# USB_Interface.net
KiCad netlist of a schematic drawn in Altium Designer
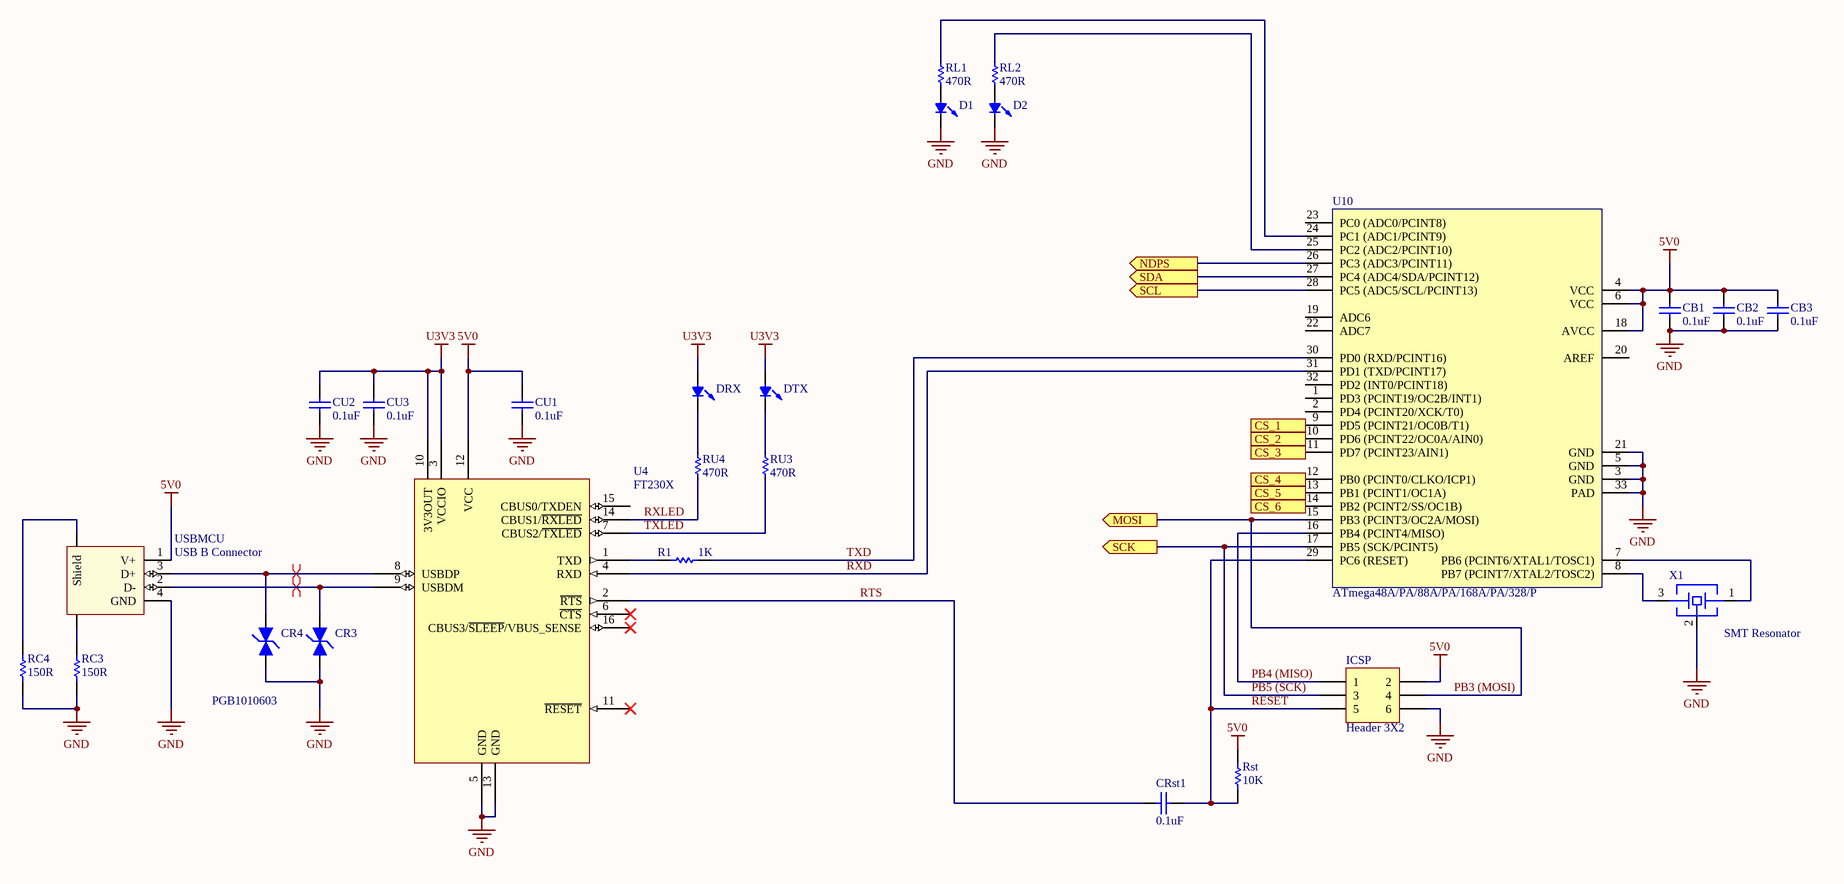
[diagram p0: USB Interface.SchDoc]

(export (version "E")
  (design (tool "Eeschema 10.0.6"))
  (components
    (comp (ref "CB1")
      (value "0.1uF")
      (footprint "0603C")
      (description "Capacitor (Semiconductor SIM Model)")
      (fields (field (name "Comment") "Cap Semi") (field (name "PUBLISHER") "Altium Limited"))
      (libsource (lib "Miscellaneous Devices") (part "Cap Semi"))
    )
    (comp (ref "CB2")
      (value "0.1uF")
      (footprint "0603C")
      (description "Capacitor (Semiconductor SIM Model)")
      (fields (field (name "Comment") "Cap Semi") (field (name "PUBLISHER") "Altium Limited"))
      (libsource (lib "Miscellaneous Devices") (part "Cap Semi"))
    )
    (comp (ref "CB3")
      (value "0.1uF")
      (footprint "0603C")
      (description "Capacitor (Semiconductor SIM Model)")
      (fields (field (name "Comment") "Cap Semi") (field (name "PUBLISHER") "Altium Limited"))
      (libsource (lib "Miscellaneous Devices") (part "Cap Semi"))
    )
    (comp (ref "CR3")
      (value "PGB1010603")
      (footprint "0603PG")
      (description "PulseGuard® Lead-Free 0603 Surface Mount Polymeric ESD Suppressors")
      (libsource (lib "DAQ System") (part "PGB1010603"))
    )
    (comp (ref "CR4")
      (value "PGB1010603")
      (footprint "0603PG")
      (description "PulseGuard® Lead-Free 0603 Surface Mount Polymeric ESD Suppressors")
      (libsource (lib "DAQ System") (part "PGB1010603"))
    )
    (comp (ref "CRst1")
      (value "0.1uF")
      (footprint "0603C")
      (description "Capacitor (Semiconductor SIM Model)")
      (fields (field (name "Comment") "Cap Semi") (field (name "PUBLISHER") "Altium Limited"))
      (libsource (lib "Miscellaneous Devices") (part "Cap Semi"))
    )
    (comp (ref "CU1")
      (value "0.1uF")
      (footprint "0603C")
      (description "Capacitor (Semiconductor SIM Model)")
      (fields (field (name "Comment") "Cap Semi") (field (name "PUBLISHER") "Altium Limited"))
      (libsource (lib "Miscellaneous Devices") (part "Cap Semi"))
    )
    (comp (ref "CU2")
      (value "0.1uF")
      (footprint "0603C")
      (description "Capacitor (Semiconductor SIM Model)")
      (fields (field (name "Comment") "Cap Semi") (field (name "PUBLISHER") "Altium Limited"))
      (libsource (lib "Miscellaneous Devices") (part "Cap Semi"))
    )
    (comp (ref "CU3")
      (value "0.1uF")
      (footprint "0603C")
      (description "Capacitor (Semiconductor SIM Model)")
      (fields (field (name "Comment") "Cap Semi") (field (name "PUBLISHER") "Altium Limited"))
      (libsource (lib "Miscellaneous Devices") (part "Cap Semi"))
    )
    (comp (ref "D1")
      (value "LED0")
      (footprint "T1 LED")
      (description "T 1 3/4 LED")
      (fields (field (name "PUBLISHER") "Altium Limited"))
      (libsource (lib "Miscellaneous Devices") (part "LED0"))
    )
    (comp (ref "D2")
      (value "LED0")
      (footprint "T1 LED")
      (description "T 1 3/4 LED")
      (fields (field (name "PUBLISHER") "Altium Limited"))
      (libsource (lib "Miscellaneous Devices") (part "LED0"))
    )
    (comp (ref "DRX")
      (value "LED0")
      (footprint "T1 LED")
      (description "T 1 3/4 LED")
      (fields (field (name "PUBLISHER") "Altium Limited"))
      (libsource (lib "Miscellaneous Devices") (part "LED0"))
    )
    (comp (ref "DTX")
      (value "LED0")
      (footprint "T1 LED")
      (description "T 1 3/4 LED")
      (fields (field (name "PUBLISHER") "Altium Limited"))
      (libsource (lib "Miscellaneous Devices") (part "LED0"))
    )
    (comp (ref "ICSP")
      (value "Header 3X2")
      (footprint "HDR2X3")
      (description "Header, 3-Pin, Dual row")
      (fields (field (name "PUBLISHER") "Altium Limited"))
      (libsource (lib "Miscellaneous Connectors") (part "Header 3X2"))
    )
    (comp (ref "R1")
      (value "1K")
      (footprint "0603R")
      (description "Semiconductor Resistor")
      (fields (field (name "Comment") "Res Semi") (field (name "PUBLISHER") "Altium Limited"))
      (libsource (lib "Miscellaneous Devices") (part "Res Semi"))
    )
    (comp (ref "RC3")
      (value "150R")
      (footprint "1206R")
      (description "Semiconductor Resistor")
      (fields (field (name "Comment") "Res Semi") (field (name "PUBLISHER") "Altium Limited"))
      (libsource (lib "Miscellaneous Devices") (part "Res Semi"))
    )
    (comp (ref "RC4")
      (value "150R")
      (footprint "1206R")
      (description "Semiconductor Resistor")
      (fields (field (name "Comment") "Res Semi") (field (name "PUBLISHER") "Altium Limited"))
      (libsource (lib "Miscellaneous Devices") (part "Res Semi"))
    )
    (comp (ref "RL1")
      (value "470R")
      (footprint "0603R")
      (description "Semiconductor Resistor")
      (fields (field (name "Comment") "Res Semi Small") (field (name "PUBLISHER") "Altium Limited"))
      (libsource (lib "Miscellaneous Devices") (part "Res Semi Small"))
    )
    (comp (ref "RL2")
      (value "470R")
      (footprint "0603R")
      (description "Semiconductor Resistor")
      (fields (field (name "Comment") "Res Semi Small") (field (name "PUBLISHER") "Altium Limited"))
      (libsource (lib "Miscellaneous Devices") (part "Res Semi Small"))
    )
    (comp (ref "Rst")
      (value "10K")
      (footprint "0603R")
      (description "Semiconductor Resistor")
      (fields (field (name "Comment") "Res Semi") (field (name "PUBLISHER") "Altium Limited"))
      (libsource (lib "Miscellaneous Devices") (part "Res Semi"))
    )
    (comp (ref "RU3")
      (value "470R")
      (footprint "0603R")
      (description "Semiconductor Resistor")
      (fields (field (name "Comment") "Res Semi Small") (field (name "PUBLISHER") "Altium Limited"))
      (libsource (lib "Miscellaneous Devices") (part "Res Semi Small"))
    )
    (comp (ref "RU4")
      (value "470R")
      (footprint "0603R")
      (description "Semiconductor Resistor")
      (fields (field (name "Comment") "Res Semi Small") (field (name "PUBLISHER") "Altium Limited"))
      (libsource (lib "Miscellaneous Devices") (part "Res Semi Small"))
    )
    (comp (ref "U4")
      (value "FT230X")
      (footprint "SOP635P600-16AN")
      (description "USB To Basic Serial Bridge IC")
      (libsource (lib "ICs") (part "FT230X"))
    )
    (comp (ref "U10")
      (value "ATmega48A/PA/88A/PA/168A/PA/328/P")
      (footprint "TQFP80P900X900X120-32N")
      (description "Atmel 8-bit Microcontroller with 4/8/16/32KBytes In-  System Programmable Flash")
      (libsource (lib "ICs") (part "ATmega48A/PA/88A/PA/168A/PA/328/P"))
    )
    (comp (ref "USBMCU")
      (value "USB B Connector")
      (footprint "USB Connector (type B)")
      (libsource (lib "DAQ Sstem") (part "USB B connector - Through hole"))
    )
    (comp (ref "X1")
      (value "SMT Resonator")
      (footprint "CSTCE_V")
      (description "16 MHz SMT Resonator")
      (libsource (lib "Unsorted") (part "SMT Resonator"))
    )
  )
  (nets
    (net (code "1") (name "/CS_1") (class "Default")
      (node (ref "U10") (pin "9") (pinfunction "PD5_(PCINT21/OC0B/T1)_9") (pintype "passive"))
    )
    (net (code "2") (name "/CS_2") (class "Default")
      (node (ref "U10") (pin "10") (pinfunction "PD6_(PCINT22/OC0A/AIN0)_10") (pintype "passive"))
    )
    (net (code "3") (name "/CS_3") (class "Default")
      (node (ref "U10") (pin "11") (pinfunction "PD7_(PCINT23/AIN1)_11") (pintype "passive"))
    )
    (net (code "4") (name "/CS_4") (class "Default")
      (node (ref "U10") (pin "12") (pinfunction "PB0_(PCINT0/CLKO/ICP1)_12") (pintype "passive"))
    )
    (net (code "5") (name "/CS_5") (class "Default")
      (node (ref "U10") (pin "13") (pinfunction "PB1_(PCINT1/OC1A)_13") (pintype "passive"))
    )
    (net (code "6") (name "/CS_6") (class "Default")
      (node (ref "U10") (pin "14") (pinfunction "PB2_(PCINT2/SS/OC1B)_14") (pintype "passive"))
    )
    (net (code "7") (name "/NDPS") (class "Default")
      (node (ref "U10") (pin "26") (pinfunction "PC3_(ADC3/PCINT11)_26") (pintype "passive"))
    )
    (net (code "8") (name "/PB3 (MOSI)") (class "Default")
      (node (ref "ICSP") (pin "4") (pinfunction "4_4") (pintype "passive"))
      (node (ref "U10") (pin "15") (pinfunction "PB3_(PCINT3/OC2A/MOSI)_15") (pintype "passive"))
    )
    (net (code "9") (name "/PB4 (MISO)") (class "Default")
      (node (ref "ICSP") (pin "1") (pinfunction "1_1") (pintype "passive"))
      (node (ref "U10") (pin "16") (pinfunction "PB4_(PCINT4/MISO)_16") (pintype "passive"))
    )
    (net (code "10") (name "/PB5 (SCK)") (class "Default")
      (node (ref "ICSP") (pin "3") (pinfunction "3_3") (pintype "passive"))
      (node (ref "U10") (pin "17") (pinfunction "PB5_(SCK/PCINT5)_17") (pintype "passive"))
    )
    (net (code "11") (name "/RESET") (class "Default")
      (node (ref "CRst1") (pin "2") (pinfunction "2_2") (pintype "passive"))
      (node (ref "ICSP") (pin "5") (pinfunction "5_5") (pintype "passive"))
      (node (ref "Rst") (pin "1") (pinfunction "1_1") (pintype "passive"))
      (node (ref "U10") (pin "29") (pinfunction "PC6_(RESET)_29") (pintype "passive"))
    )
    (net (code "12") (name "/RTS") (class "Default")
      (node (ref "CRst1") (pin "1") (pinfunction "1_1") (pintype "passive"))
      (node (ref "U4") (pin "2") (pinfunction "RTS_2") (pintype "output"))
    )
    (net (code "13") (name "/RXD") (class "Default")
      (node (ref "U10") (pin "31") (pinfunction "PD1_(TXD/PCINT17)_31") (pintype "passive"))
      (node (ref "U4") (pin "4") (pinfunction "RXD_4") (pintype "input"))
    )
    (net (code "14") (name "/RXLED") (class "Default")
      (node (ref "RU4") (pin "2") (pinfunction "2_2") (pintype "passive"))
      (node (ref "U4") (pin "14") (pinfunction "CBUS1/~{RXLED}_14") (pintype "bidirectional"))
    )
    (net (code "15") (name "/SCL") (class "Default")
      (node (ref "U10") (pin "28") (pinfunction "PC5_(ADC5/SCL/PCINT13)_28") (pintype "passive"))
    )
    (net (code "16") (name "/SDA") (class "Default")
      (node (ref "U10") (pin "27") (pinfunction "PC4_(ADC4/SDA/PCINT12)_27") (pintype "passive"))
    )
    (net (code "17") (name "/TXD") (class "Default")
      (node (ref "R1") (pin "2") (pinfunction "2_2") (pintype "passive"))
      (node (ref "U10") (pin "30") (pinfunction "PD0_(RXD/PCINT16)_30") (pintype "passive"))
    )
    (net (code "18") (name "/TXLED") (class "Default")
      (node (ref "RU3") (pin "2") (pinfunction "2_2") (pintype "passive"))
      (node (ref "U4") (pin "7") (pinfunction "CBUS2/~{TXLED}_7") (pintype "bidirectional"))
    )
    (net (code "19") (name "5V0") (class "Default")
      (node (ref "CB1") (pin "2") (pinfunction "2_2") (pintype "passive"))
      (node (ref "CB2") (pin "2") (pinfunction "2_2") (pintype "passive"))
      (node (ref "CB3") (pin "2") (pinfunction "2_2") (pintype "passive"))
      (node (ref "CU1") (pin "2") (pinfunction "2_2") (pintype "passive"))
      (node (ref "ICSP") (pin "2") (pinfunction "2_2") (pintype "passive"))
      (node (ref "Rst") (pin "2") (pinfunction "2_2") (pintype "passive"))
      (node (ref "U10") (pin "18") (pinfunction "AVCC_18") (pintype "passive"))
      (node (ref "U10") (pin "4") (pinfunction "VCC_4") (pintype "passive"))
      (node (ref "U10") (pin "6") (pinfunction "VCC_6") (pintype "passive"))
      (node (ref "U4") (pin "12") (pinfunction "VCC_12") (pintype "power_in"))
      (node (ref "USBMCU") (pin "1") (pinfunction "V+_1") (pintype "power_in"))
    )
    (net (code "20") (name "GND") (class "Default")
      (node (ref "CB1") (pin "1") (pinfunction "1_1") (pintype "passive"))
      (node (ref "CB2") (pin "1") (pinfunction "1_1") (pintype "passive"))
      (node (ref "CB3") (pin "1") (pinfunction "1_1") (pintype "passive"))
      (node (ref "CR3") (pin "2") (pinfunction "2_2") (pintype "passive"))
      (node (ref "CR4") (pin "2") (pinfunction "2_2") (pintype "passive"))
      (node (ref "CU1") (pin "1") (pinfunction "1_1") (pintype "passive"))
      (node (ref "CU2") (pin "1") (pinfunction "1_1") (pintype "passive"))
      (node (ref "CU3") (pin "1") (pinfunction "1_1") (pintype "passive"))
      (node (ref "D1") (pin "2") (pinfunction "2_2") (pintype "passive"))
      (node (ref "D2") (pin "2") (pinfunction "2_2") (pintype "passive"))
      (node (ref "ICSP") (pin "6") (pinfunction "6_6") (pintype "passive"))
      (node (ref "RC3") (pin "1") (pinfunction "1_1") (pintype "passive"))
      (node (ref "RC4") (pin "1") (pinfunction "1_1") (pintype "passive"))
      (node (ref "U10") (pin "21") (pinfunction "GND_21") (pintype "passive"))
      (node (ref "U10") (pin "3") (pinfunction "GND_3") (pintype "passive"))
      (node (ref "U10") (pin "33") (pinfunction "PAD_33") (pintype "passive"))
      (node (ref "U10") (pin "5") (pinfunction "GND_5") (pintype "passive"))
      (node (ref "U4") (pin "13") (pinfunction "GND_13") (pintype "power_in"))
      (node (ref "U4") (pin "5") (pinfunction "GND_5") (pintype "power_in"))
      (node (ref "USBMCU") (pin "4") (pinfunction "GND_4") (pintype "power_in"))
      (node (ref "X1") (pin "2") (pinfunction "2_2") (pintype "passive"))
    )
    (net (code "21") (name "Net-(D1-Pad1)") (class "Default")
      (node (ref "D1") (pin "1") (pinfunction "1_1") (pintype "passive"))
      (node (ref "RL1") (pin "2") (pinfunction "2_2") (pintype "passive"))
    )
    (net (code "22") (name "Net-(D2-Pad1)") (class "Default")
      (node (ref "D2") (pin "1") (pinfunction "1_1") (pintype "passive"))
      (node (ref "RL2") (pin "2") (pinfunction "2_2") (pintype "passive"))
    )
    (net (code "23") (name "Net-(DRX-Pad2)") (class "Default")
      (node (ref "DRX") (pin "2") (pinfunction "2_2") (pintype "passive"))
      (node (ref "RU4") (pin "1") (pinfunction "1_1") (pintype "passive"))
    )
    (net (code "24") (name "Net-(DTX-Pad2)") (class "Default")
      (node (ref "DTX") (pin "2") (pinfunction "2_2") (pintype "passive"))
      (node (ref "RU3") (pin "1") (pinfunction "1_1") (pintype "passive"))
    )
    (net (code "25") (name "Net-(U4-TXD)") (class "Default")
      (node (ref "R1") (pin "1") (pinfunction "1_1") (pintype "passive"))
      (node (ref "U4") (pin "1") (pinfunction "TXD_1") (pintype "output"))
    )
    (net (code "26") (name "Net-(U4-USBDM)") (class "Default")
      (node (ref "CR3") (pin "1") (pinfunction "1_1") (pintype "passive"))
      (node (ref "U4") (pin "9") (pinfunction "USBDM_9") (pintype "bidirectional"))
      (node (ref "USBMCU") (pin "2") (pinfunction "D-_2") (pintype "bidirectional"))
    )
    (net (code "27") (name "Net-(U4-USBDP)") (class "Default")
      (node (ref "CR4") (pin "1") (pinfunction "1_1") (pintype "passive"))
      (node (ref "U4") (pin "8") (pinfunction "USBDP_8") (pintype "bidirectional"))
      (node (ref "USBMCU") (pin "3") (pinfunction "D+_3") (pintype "bidirectional"))
    )
    (net (code "28") (name "Net-(U10-PB6_(PCINT6{slash}XTAL1{slash}TOSC1))") (class "Default")
      (node (ref "U10") (pin "7") (pinfunction "PB6_(PCINT6/XTAL1/TOSC1)_7") (pintype "passive"))
      (node (ref "X1") (pin "1") (pinfunction "1_1") (pintype "passive"))
    )
    (net (code "29") (name "Net-(U10-PB7_(PCINT7{slash}XTAL2{slash}TOSC2))") (class "Default")
      (node (ref "U10") (pin "8") (pinfunction "PB7_(PCINT7/XTAL2/TOSC2)_8") (pintype "passive"))
      (node (ref "X1") (pin "3") (pinfunction "3_3") (pintype "passive"))
    )
    (net (code "30") (name "Net-(U10-PC1_(ADC1{slash}PCINT9))") (class "Default")
      (node (ref "RL1") (pin "1") (pinfunction "1_1") (pintype "passive"))
      (node (ref "U10") (pin "24") (pinfunction "PC1_(ADC1/PCINT9)_24") (pintype "passive"))
    )
    (net (code "31") (name "Net-(U10-PC2_(ADC2{slash}PCINT10))") (class "Default")
      (node (ref "RL2") (pin "1") (pinfunction "1_1") (pintype "passive"))
      (node (ref "U10") (pin "25") (pinfunction "PC2_(ADC2/PCINT10)_25") (pintype "passive"))
    )
    (net (code "32") (name "Net-(USBMCU-Gnd)") (class "Default")
      (node (ref "RC3") (pin "2") (pinfunction "2_2") (pintype "passive"))
      (node (ref "USBMCU") (pin "5") (pinfunction "Gnd_5") (pintype "passive"))
    )
    (net (code "33") (name "Net-(USBMCU-Shield)") (class "Default")
      (node (ref "RC4") (pin "2") (pinfunction "2_2") (pintype "passive"))
      (node (ref "USBMCU") (pin "6") (pinfunction "Shield_6") (pintype "passive"))
    )
    (net (code "34") (name "U3V3") (class "Default")
      (node (ref "CU2") (pin "2") (pinfunction "2_2") (pintype "passive"))
      (node (ref "CU3") (pin "2") (pinfunction "2_2") (pintype "passive"))
      (node (ref "DRX") (pin "1") (pinfunction "1_1") (pintype "passive"))
      (node (ref "DTX") (pin "1") (pinfunction "1_1") (pintype "passive"))
      (node (ref "U4") (pin "10") (pinfunction "3V3OUT_10") (pintype "power_in"))
      (node (ref "U4") (pin "3") (pinfunction "VCCIO_3") (pintype "power_in"))
    )
    (net (code "35") (name "unconnected-(U4-CBUS0{slash}TXDEN-Pad15)") (class "Default")
      (node (ref "U4") (pin "15") (pinfunction "CBUS0/TXDEN_15") (pintype "bidirectional"))
    )
    (net (code "36") (name "unconnected-(U4-CBUS3{slash}~{SLEEP}{slash}VBUS_SENSE-Pad16)") (class "Default")
      (node (ref "U4") (pin "16") (pinfunction "CBUS3/~{SLEEP}/VBUS_SENSE_16") (pintype "bidirectional+no_connect"))
    )
    (net (code "37") (name "unconnected-(U4-CTS-Pad6)") (class "Default")
      (node (ref "U4") (pin "6") (pinfunction "CTS_6") (pintype "input+no_connect"))
    )
    (net (code "38") (name "unconnected-(U4-NC-Pad8)") (class "Default")
      (node (ref "U4") (pin "8") (pinfunction "NC_8") (pintype "passive"))
    )
    (net (code "39") (name "unconnected-(U4-NC-Pad24)") (class "Default")
      (node (ref "U4") (pin "24") (pinfunction "NC_24") (pintype "passive"))
    )
    (net (code "40") (name "unconnected-(U4-~{RESET}-Pad11)") (class "Default")
      (node (ref "U4") (pin "11") (pinfunction "~{RESET}_11") (pintype "input+no_connect"))
    )
    (net (code "41") (name "unconnected-(U10-ADC6-Pad19)") (class "Default")
      (node (ref "U10") (pin "19") (pinfunction "ADC6_19") (pintype "passive"))
    )
    (net (code "42") (name "unconnected-(U10-ADC7-Pad22)") (class "Default")
      (node (ref "U10") (pin "22") (pinfunction "ADC7_22") (pintype "passive"))
    )
    (net (code "43") (name "unconnected-(U10-AREF-Pad20)") (class "Default")
      (node (ref "U10") (pin "20") (pinfunction "AREF_20") (pintype "passive"))
    )
    (net (code "44") (name "unconnected-(U10-PC0_(ADC0{slash}PCINT8)-Pad23)") (class "Default")
      (node (ref "U10") (pin "23") (pinfunction "PC0_(ADC0/PCINT8)_23") (pintype "passive"))
    )
    (net (code "45") (name "unconnected-(U10-PD2_(INT0{slash}PCINT18)-Pad32)") (class "Default")
      (node (ref "U10") (pin "32") (pinfunction "PD2_(INT0/PCINT18)_32") (pintype "passive"))
    )
    (net (code "46") (name "unconnected-(U10-PD3_(PCINT19{slash}OC2B{slash}INT1)-Pad1)") (class "Default")
      (node (ref "U10") (pin "1") (pinfunction "PD3_(PCINT19/OC2B/INT1)_1") (pintype "passive"))
    )
    (net (code "47") (name "unconnected-(U10-PD4_(PCINT20{slash}XCK{slash}T0)-Pad2)") (class "Default")
      (node (ref "U10") (pin "2") (pinfunction "PD4_(PCINT20/XCK/T0)_2") (pintype "passive"))
    )
  )
)
